# HDMI.net
KiCad netlist of a schematic drawn in Altium Designer
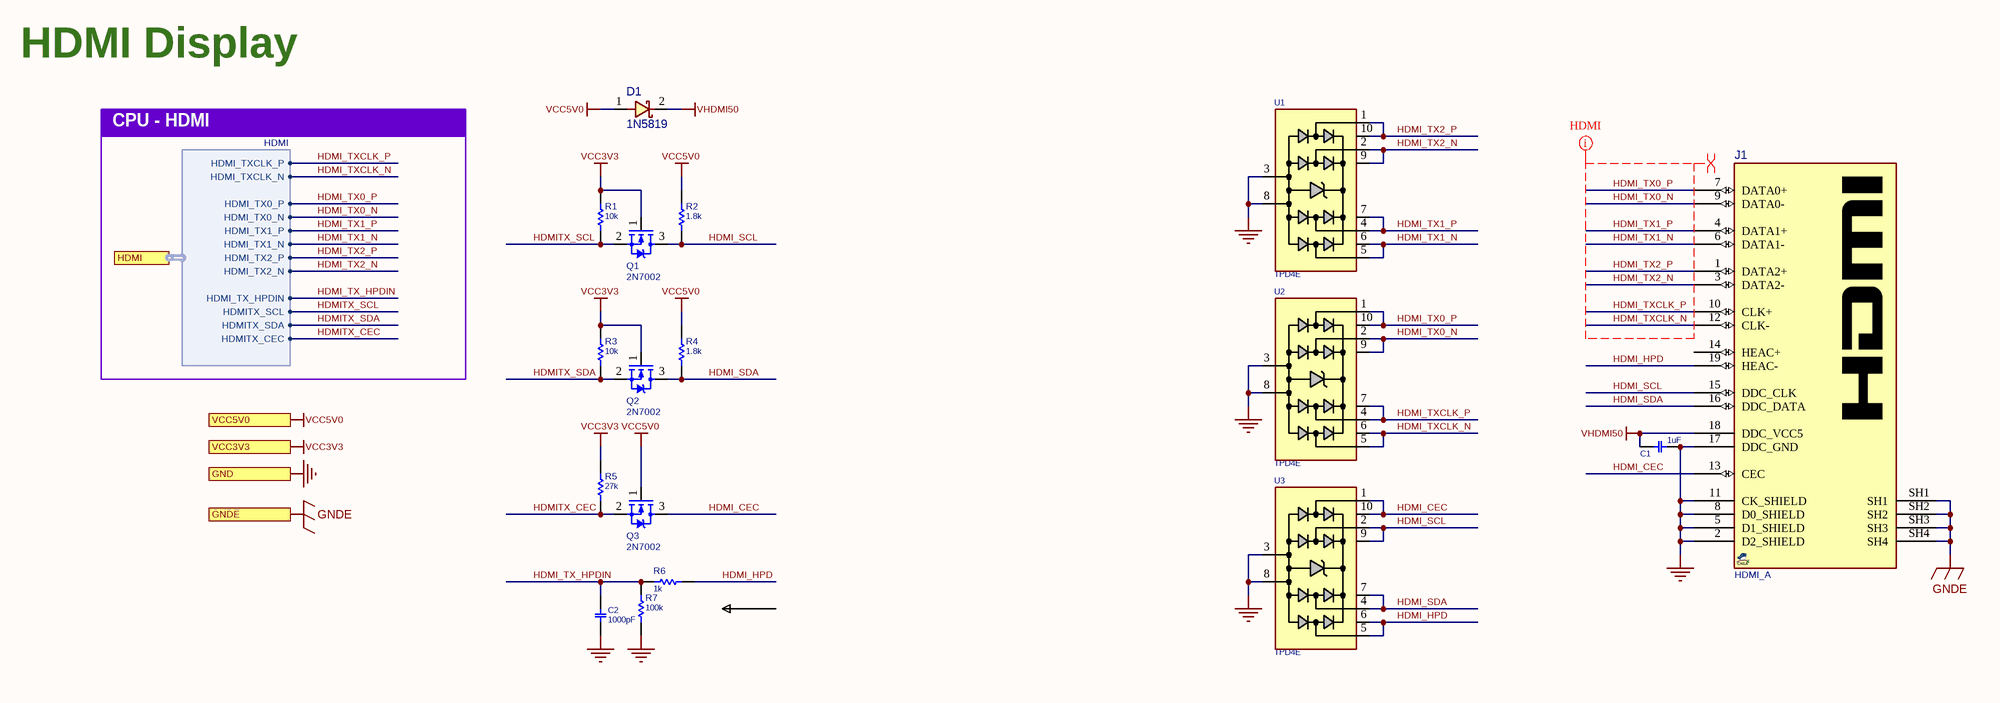
[diagram p0: HDMI.SchDoc]

(export (version "E")
  (design (tool "Eeschema 10.0.6"))
  (components
    (comp (ref "C1")
      (value "1uF")
      (footprint "C0402")
      (description "CAP, MLCC")
      (fields (field (name "MANF_P#") "CL05A105KO5NNND") (field (name "MANF") "Samsung"))
      (libsource (lib "passive_smd") (part "CAP_SMD_MLCC"))
    )
    (comp (ref "C2")
      (value "1000pF")
      (footprint "C0402")
      (description "CAP, MLCC")
      (fields (field (name "MANF_P#") "CC0402JRNPO9BN102") (field (name "MANF") "Yageo"))
      (libsource (lib "passive_smd") (part "CAP_SMD_MLCC"))
    )
    (comp (ref "D1")
      (value "1N5819")
      (footprint "D_SOD123W")
      (description "DIODE, SCHOTTKY, 40V, 1A")
      (fields (field (name "MANF") "DIODES") (field (name "MANF_P#") "1N5819HW-7-F"))
      (libsource (lib "diode") (part "DIODE_SMD_SCHOTTKY_1N5819"))
    )
    (comp (ref "J1")
      (value "HDMI_A")
      (footprint "HDMI_A")
      (description "CONN, HDMI, Receptacle, TYPE A, 19P, RIGH-ANGLE")
      (fields
        (field (name "MANF") "Molex, WURTH")
        (field (name "MANF_P#") "208658-1051, 47151-0001, 500254-1927")
      )
      (libsource (lib "conn_disp_hdmi") (part "CONN_HDMI_A"))
    )
    (comp (ref "Q1")
      (value "2N7002")
      (footprint "SOT323_3")
      (description "MOSFET, N-CH, 60V, 0.3A, SOT323")
      (fields
        (field (name "MANF_P#") "2N7002BKW, 2N7002KW, 2N7002W")
        (field (name "MANF") "NXP Semiconductors")
      )
      (libsource (lib "transistor_fet") (part "MOSN_2N7002_SOT323"))
    )
    (comp (ref "Q2")
      (value "2N7002")
      (footprint "SOT323_3")
      (description "MOSFET, N-CH, 60V, 0.3A, SOT323")
      (fields
        (field (name "MANF_P#") "2N7002BKW, 2N7002KW, 2N7002W")
        (field (name "MANF") "NXP Semiconductors")
      )
      (libsource (lib "transistor_fet") (part "MOSN_2N7002_SOT323"))
    )
    (comp (ref "Q3")
      (value "2N7002")
      (footprint "SOT323_3")
      (description "MOSFET, N-CH, 60V, 0.3A, SOT323")
      (fields
        (field (name "MANF_P#") "2N7002BKW, 2N7002KW, 2N7002W")
        (field (name "MANF") "NXP Semiconductors")
      )
      (libsource (lib "transistor_fet") (part "MOSN_2N7002_SOT323"))
    )
    (comp (ref "R1")
      (value "10k")
      (footprint "R0402")
      (description "RESISTOR, SMD")
      (libsource (lib "passive_res_smd") (part "RES_SMD"))
    )
    (comp (ref "R2")
      (value "1.8k")
      (footprint "R0402")
      (description "RESISTOR, SMD")
      (libsource (lib "passive_res_smd") (part "RES_SMD"))
    )
    (comp (ref "R3")
      (value "10k")
      (footprint "R0402")
      (description "RESISTOR, SMD")
      (libsource (lib "passive_res_smd") (part "RES_SMD"))
    )
    (comp (ref "R4")
      (value "1.8k")
      (footprint "R0402")
      (description "RESISTOR, SMD")
      (libsource (lib "passive_res_smd") (part "RES_SMD"))
    )
    (comp (ref "R5")
      (value "27k")
      (footprint "R0402")
      (description "RESISTOR, SMD")
      (libsource (lib "passive_res_smd") (part "RES_SMD"))
    )
    (comp (ref "R6")
      (value "1k")
      (footprint "R0402")
      (description "RESISTOR, SMD")
      (libsource (lib "passive_res_smd") (part "RES_SMD"))
    )
    (comp (ref "R7")
      (value "100k")
      (footprint "R0402")
      (description "RESISTOR, SMD")
      (libsource (lib "passive_res_smd") (part "RES_SMD"))
    )
    (comp (ref "U1")
      (value "TPD4E")
      (footprint "SON50_10_2510")
      (description "TVS, ESD PROTECT, 4CH,")
      (fields (field (name "MANF_P#") "TPD4E05U06DQA") (field (name "MANF") "Texas Instruments"))
      (libsource (lib "protect_tvs_esd_fuse") (part "TVS_X4_TPD4E05U06"))
    )
    (comp (ref "U2")
      (value "TPD4E")
      (footprint "SON50_10_2510")
      (description "TVS, ESD PROTECT, 4CH,")
      (fields (field (name "MANF_P#") "TPD4E05U06DQA") (field (name "MANF") "Texas Instruments"))
      (libsource (lib "protect_tvs_esd_fuse") (part "TVS_X4_TPD4E05U06"))
    )
    (comp (ref "U3")
      (value "TPD4E")
      (footprint "SON50_10_2510")
      (description "TVS, ESD PROTECT, 4CH,")
      (fields (field (name "MANF_P#") "TPD4E05U06DQA") (field (name "MANF") "Texas Instruments"))
      (libsource (lib "protect_tvs_esd_fuse") (part "TVS_X4_TPD4E05U06"))
    )
  )
  (nets
    (net (code "2") (name "/HDMITX_CEC") (class "Default")
      (node (ref "Q3") (pin "2") (pinfunction "SOURCE_2") (pintype "passive"))
      (node (ref "R5") (pin "2") (pinfunction "2_2") (pintype "passive"))
    )
    (net (code "3") (name "/HDMITX_SCL") (class "Default")
      (node (ref "Q1") (pin "2") (pinfunction "SOURCE_2") (pintype "passive"))
      (node (ref "R1") (pin "2") (pinfunction "2_2") (pintype "passive"))
    )
    (net (code "4") (name "/HDMITX_SDA") (class "Default")
      (node (ref "Q2") (pin "2") (pinfunction "SOURCE_2") (pintype "passive"))
      (node (ref "R3") (pin "2") (pinfunction "2_2") (pintype "passive"))
    )
    (net (code "5") (name "/HDMI_CEC") (class "Default")
      (node (ref "J1") (pin "13") (pinfunction "CEC_13") (pintype "bidirectional"))
      (node (ref "Q3") (pin "3") (pinfunction "DRAIN_3") (pintype "passive"))
      (node (ref "U3") (pin "1") (pinfunction "1_1") (pintype "passive"))
      (node (ref "U3") (pin "10") (pinfunction "10_10") (pintype "passive"))
    )
    (net (code "6") (name "/HDMI_HPD") (class "Default")
      (node (ref "J1") (pin "19") (pinfunction "HEAC-_19") (pintype "bidirectional"))
      (node (ref "R6") (pin "2") (pinfunction "2_2") (pintype "passive"))
      (node (ref "U3") (pin "5") (pinfunction "5_5") (pintype "passive"))
      (node (ref "U3") (pin "6") (pinfunction "6_6") (pintype "passive"))
    )
    (net (code "7") (name "/HDMI_SCL") (class "Default")
      (node (ref "J1") (pin "15") (pinfunction "DDC_CLK_15") (pintype "bidirectional"))
      (node (ref "Q1") (pin "3") (pinfunction "DRAIN_3") (pintype "passive"))
      (node (ref "R2") (pin "2") (pinfunction "2_2") (pintype "passive"))
      (node (ref "U3") (pin "2") (pinfunction "2_2") (pintype "passive"))
      (node (ref "U3") (pin "9") (pinfunction "9_9") (pintype "passive"))
    )
    (net (code "8") (name "/HDMI_SDA") (class "Default")
      (node (ref "J1") (pin "16") (pinfunction "DDC_DATA_16") (pintype "bidirectional"))
      (node (ref "Q2") (pin "3") (pinfunction "DRAIN_3") (pintype "passive"))
      (node (ref "R4") (pin "2") (pinfunction "2_2") (pintype "passive"))
      (node (ref "U3") (pin "4") (pinfunction "4_4") (pintype "passive"))
      (node (ref "U3") (pin "7") (pinfunction "7_7") (pintype "passive"))
    )
    (net (code "9") (name "/HDMI_TX0_N") (class "Default")
      (node (ref "J1") (pin "9") (pinfunction "DATA0-_9") (pintype "bidirectional"))
      (node (ref "U2") (pin "2") (pinfunction "2_2") (pintype "passive"))
      (node (ref "U2") (pin "9") (pinfunction "9_9") (pintype "passive"))
    )
    (net (code "10") (name "/HDMI_TX0_P") (class "Default")
      (node (ref "J1") (pin "7") (pinfunction "DATA0+_7") (pintype "bidirectional"))
      (node (ref "U2") (pin "1") (pinfunction "1_1") (pintype "passive"))
      (node (ref "U2") (pin "10") (pinfunction "10_10") (pintype "passive"))
    )
    (net (code "11") (name "/HDMI_TX1_N") (class "Default")
      (node (ref "J1") (pin "6") (pinfunction "DATA1-_6") (pintype "bidirectional"))
      (node (ref "U1") (pin "5") (pinfunction "5_5") (pintype "passive"))
      (node (ref "U1") (pin "6") (pinfunction "6_6") (pintype "passive"))
    )
    (net (code "12") (name "/HDMI_TX1_P") (class "Default")
      (node (ref "J1") (pin "4") (pinfunction "DATA1+_4") (pintype "bidirectional"))
      (node (ref "U1") (pin "4") (pinfunction "4_4") (pintype "passive"))
      (node (ref "U1") (pin "7") (pinfunction "7_7") (pintype "passive"))
    )
    (net (code "13") (name "/HDMI_TX2_N") (class "Default")
      (node (ref "J1") (pin "3") (pinfunction "DATA2-_3") (pintype "bidirectional"))
      (node (ref "U1") (pin "2") (pinfunction "2_2") (pintype "passive"))
      (node (ref "U1") (pin "9") (pinfunction "9_9") (pintype "passive"))
    )
    (net (code "14") (name "/HDMI_TX2_P") (class "Default")
      (node (ref "J1") (pin "1") (pinfunction "DATA2+_1") (pintype "bidirectional"))
      (node (ref "U1") (pin "1") (pinfunction "1_1") (pintype "passive"))
      (node (ref "U1") (pin "10") (pinfunction "10_10") (pintype "passive"))
    )
    (net (code "15") (name "/HDMI_TXCLK_N") (class "Default")
      (node (ref "J1") (pin "12") (pinfunction "CLK-_12") (pintype "bidirectional"))
      (node (ref "U2") (pin "5") (pinfunction "5_5") (pintype "passive"))
      (node (ref "U2") (pin "6") (pinfunction "6_6") (pintype "passive"))
    )
    (net (code "16") (name "/HDMI_TXCLK_P") (class "Default")
      (node (ref "J1") (pin "10") (pinfunction "CLK+_10") (pintype "bidirectional"))
      (node (ref "U2") (pin "4") (pinfunction "4_4") (pintype "passive"))
      (node (ref "U2") (pin "7") (pinfunction "7_7") (pintype "passive"))
    )
    (net (code "17") (name "/HDMI_TX_HPDIN") (class "Default")
      (node (ref "C2") (pin "2") (pinfunction "2_2") (pintype "passive"))
      (node (ref "R6") (pin "1") (pinfunction "1_1") (pintype "passive"))
      (node (ref "R7") (pin "2") (pinfunction "2_2") (pintype "passive"))
    )
    (net (code "19") (name "GND") (class "Default")
      (node (ref "C1") (pin "1") (pinfunction "1_1") (pintype "passive"))
      (node (ref "C2") (pin "1") (pinfunction "1_1") (pintype "passive"))
      (node (ref "J1") (pin "11") (pinfunction "CK_SHIELD_11") (pintype "passive"))
      (node (ref "J1") (pin "17") (pinfunction "DDC_GND_17") (pintype "passive"))
      (node (ref "J1") (pin "2") (pinfunction "D2_SHIELD_2") (pintype "passive"))
      (node (ref "J1") (pin "5") (pinfunction "D1_SHIELD_5") (pintype "passive"))
      (node (ref "J1") (pin "8") (pinfunction "D0_SHIELD_8") (pintype "passive"))
      (node (ref "R7") (pin "1") (pinfunction "1_1") (pintype "passive"))
      (node (ref "U1") (pin "3") (pinfunction "3_3") (pintype "passive"))
      (node (ref "U1") (pin "8") (pinfunction "8_8") (pintype "passive"))
      (node (ref "U2") (pin "3") (pinfunction "3_3") (pintype "passive"))
      (node (ref "U2") (pin "8") (pinfunction "8_8") (pintype "passive"))
      (node (ref "U3") (pin "3") (pinfunction "3_3") (pintype "passive"))
      (node (ref "U3") (pin "8") (pinfunction "8_8") (pintype "passive"))
    )
    (net (code "20") (name "GNDE") (class "Default")
      (node (ref "J1") (pin "SH1") (pinfunction "SH1_SH1") (pintype "passive"))
      (node (ref "J1") (pin "SH2") (pinfunction "SH2_SH2") (pintype "passive"))
      (node (ref "J1") (pin "SH3") (pinfunction "SH3_SH3") (pintype "passive"))
      (node (ref "J1") (pin "SH4") (pinfunction "SH4_SH4") (pintype "passive"))
    )
    (net (code "21") (name "VCC3V3") (class "Default")
      (node (ref "Q1") (pin "1") (pinfunction "GATE_1") (pintype "passive"))
      (node (ref "Q2") (pin "1") (pinfunction "GATE_1") (pintype "passive"))
      (node (ref "R1") (pin "1") (pinfunction "1_1") (pintype "passive"))
      (node (ref "R3") (pin "1") (pinfunction "1_1") (pintype "passive"))
      (node (ref "R5") (pin "1") (pinfunction "1_1") (pintype "passive"))
    )
    (net (code "22") (name "VCC5V0") (class "Default")
      (node (ref "D1") (pin "1") (pinfunction "1_1") (pintype "passive"))
      (node (ref "Q3") (pin "1") (pinfunction "GATE_1") (pintype "passive"))
      (node (ref "R2") (pin "1") (pinfunction "1_1") (pintype "passive"))
      (node (ref "R4") (pin "1") (pinfunction "1_1") (pintype "passive"))
    )
    (net (code "23") (name "VHDMI50") (class "Default")
      (node (ref "C1") (pin "2") (pinfunction "2_2") (pintype "passive"))
      (node (ref "D1") (pin "2") (pinfunction "2_2") (pintype "passive"))
      (node (ref "J1") (pin "18") (pinfunction "DDC_VCC5_18") (pintype "passive"))
    )
    (net (code "24") (name "unconnected-(J1-HEAC+-Pad14)") (class "Default")
      (node (ref "J1") (pin "14") (pinfunction "HEAC+_14") (pintype "bidirectional"))
    )
  )
)
